# Power_Decap_2.net
KiCad netlist of a schematic drawn in Altium Designer
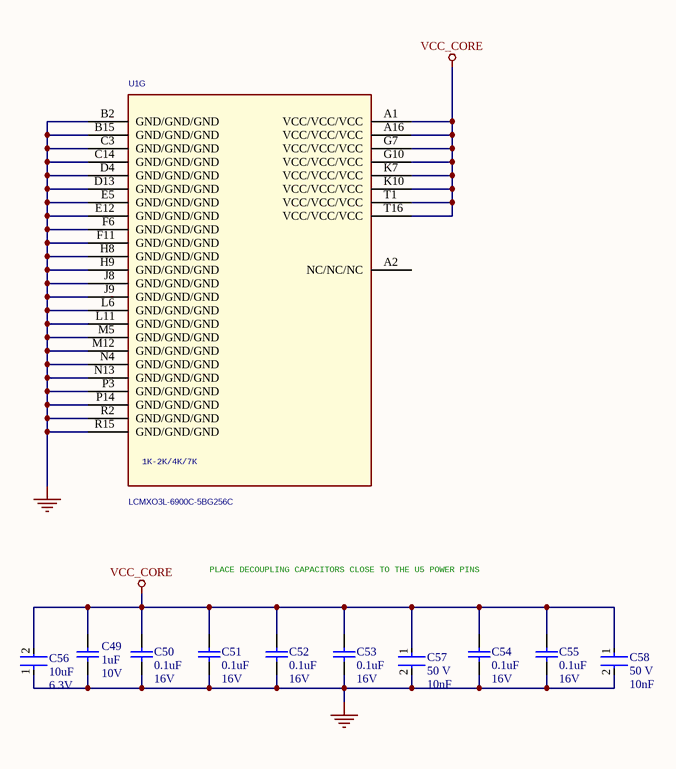
[diagram p0: Power_Decap 2.SchDoc]

(export (version "E")
  (design (tool "Eeschema 10.0.6"))
  (components
    (comp (ref "C49")
      (value "1uF")
      (footprint "CAPC1608X90X35ML15T15")
      (fields
        (field (name "MANUFACTURER") "Kemet")
        (field (name "PART NUMBER") "C0603C105K8RACTU")
        (field (name "VOLTAGE") "10V")
      )
      (libsource (lib "Altium Content Vault") (part "CAP"))
    )
    (comp (ref "C50")
      (value "0.1uF")
      (footprint "CAPC1608X87X35ML15T15")
      (description "Ceramic Capacitor 0.1uF 16V +-10% X7R0603")
      (fields
        (field (name "PART NUMBER") "C0603C104M4RACTU")
        (field (name "MANUFACTURER") "Kemet")
        (field (name "VOLTAGE") "16V")
      )
      (libsource (lib "Altium Content Vault") (part "CAP"))
    )
    (comp (ref "C51")
      (value "0.1uF")
      (footprint "CAPC1608X87X35ML15T15")
      (description "Ceramic Capacitor 0.1uF 16V +-10% X7R0603")
      (fields
        (field (name "PART NUMBER") "C0603C104M4RACTU")
        (field (name "MANUFACTURER") "Kemet")
        (field (name "VOLTAGE") "16V")
      )
      (libsource (lib "Altium Content Vault") (part "CAP"))
    )
    (comp (ref "C52")
      (value "0.1uF")
      (footprint "CAPC1608X87X35ML15T15")
      (description "Ceramic Capacitor 0.1uF 16V +-10% X7R0603")
      (fields
        (field (name "PART NUMBER") "C0603C104M4RACTU")
        (field (name "MANUFACTURER") "Kemet")
        (field (name "VOLTAGE") "16V")
      )
      (libsource (lib "Altium Content Vault") (part "CAP"))
    )
    (comp (ref "C53")
      (value "0.1uF")
      (footprint "CAPC1608X87X35ML15T15")
      (description "Ceramic Capacitor 0.1uF 16V +-10% X7R0603")
      (fields
        (field (name "PART NUMBER") "C0603C104M4RACTU")
        (field (name "MANUFACTURER") "Kemet")
        (field (name "VOLTAGE") "16V")
      )
      (libsource (lib "Altium Content Vault") (part "CAP"))
    )
    (comp (ref "C54")
      (value "0.1uF")
      (footprint "CAPC1608X87X35ML15T15")
      (description "Ceramic Capacitor 0.1uF 16V +-10% X7R0603")
      (fields
        (field (name "PART NUMBER") "C0603C104M4RACTU")
        (field (name "MANUFACTURER") "Kemet")
        (field (name "VOLTAGE") "16V")
      )
      (libsource (lib "Altium Content Vault") (part "CAP"))
    )
    (comp (ref "C55")
      (value "0.1uF")
      (footprint "CAPC1608X87X35ML15T15")
      (description "Ceramic Capacitor 0.1uF 16V +-10% X7R0603")
      (fields
        (field (name "PART NUMBER") "C0603C104M4RACTU")
        (field (name "MANUFACTURER") "Kemet")
        (field (name "VOLTAGE") "16V")
      )
      (libsource (lib "Altium Content Vault") (part "CAP"))
    )
    (comp (ref "C56")
      (value "10uF")
      (footprint "FP-CL10-IPC_C")
      (description "Cap Ceramic 10uF 6.3V X5R ±20% Pad SMD 0603 +85°C T/R")
      (fields
        (field (name "VOLTAGE") "6.3V")
        (field (name "TOLERANCE") "20%")
        (field (name "MANUFACTURER") "Samsung")
      )
      (libsource (lib "Altium Content Vault") (part "b4654b650e69147ec39a6b967a45e02"))
    )
    (comp (ref "C57")
      (value "10nF")
      (footprint "FP-C0805C-DN-MFG")
      (description "CAP CER 10000PF 50V X7R 0805")
      (fields
        (field (name "VOLTAGE") "50 V")
        (field (name "PART NUMBER") "C0805C103K5RACAUTO")
        (field (name "MANUFACTURER") "KEMET")
      )
      (libsource (lib "Altium Content Vault") (part "b4654b650e69147ec39a6b967a45e02"))
    )
    (comp (ref "C58")
      (value "10nF")
      (footprint "FP-C0805C-DN-MFG")
      (description "CAP CER 10000PF 50V X7R 0805")
      (fields
        (field (name "VOLTAGE") "50 V")
        (field (name "PART NUMBER") "C0805C103K5RACAUTO")
        (field (name "MANUFACTURER") "KEMET")
      )
      (libsource (lib "Altium Content Vault") (part "b4654b650e69147ec39a6b967a45e02"))
    )
    (comp (ref "U1")
      (value "LCMXO3L-6900C-5BG256C")
      (footprint "BGA256C80P16X16_1400X1400X170")
      (description "IC FPGA 6864LUTS 256BGA")
      (fields (field (name "MANUFACTURER") "Lattice semi"))
      (libsource (lib "*") (part "LCMXO3L-1K/2K/4K/7K-BG256"))
    )
  )
  (nets
    (net (code "1") (name "GND") (class "Default")
      (node (ref "C49") (pin "1") (pinfunction "1_1") (pintype "passive"))
      (node (ref "C50") (pin "2") (pinfunction "2_2") (pintype "passive"))
      (node (ref "C51") (pin "2") (pinfunction "2_2") (pintype "passive"))
      (node (ref "C52") (pin "2") (pinfunction "2_2") (pintype "passive"))
      (node (ref "C53") (pin "2") (pinfunction "2_2") (pintype "passive"))
      (node (ref "C54") (pin "2") (pinfunction "2_2") (pintype "passive"))
      (node (ref "C55") (pin "2") (pinfunction "2_2") (pintype "passive"))
      (node (ref "C56") (pin "1") (pinfunction "1_1") (pintype "passive"))
      (node (ref "C57") (pin "2") (pinfunction "2_2") (pintype "passive"))
      (node (ref "C58") (pin "2") (pinfunction "2_2") (pintype "passive"))
      (node (ref "U1") (pin "B15") (pinfunction "GND/GND/GND_B15") (pintype "power_in"))
      (node (ref "U1") (pin "B2") (pinfunction "GND/GND/GND_B2") (pintype "power_in"))
      (node (ref "U1") (pin "C14") (pinfunction "GND/GND/GND_C14") (pintype "power_in"))
      (node (ref "U1") (pin "C3") (pinfunction "GND/GND/GND_C3") (pintype "power_in"))
      (node (ref "U1") (pin "D13") (pinfunction "GND/GND/GND_D13") (pintype "power_in"))
      (node (ref "U1") (pin "D4") (pinfunction "GND/GND/GND_D4") (pintype "power_in"))
      (node (ref "U1") (pin "E12") (pinfunction "GND/GND/GND_E12") (pintype "power_in"))
      (node (ref "U1") (pin "E5") (pinfunction "GND/GND/GND_E5") (pintype "power_in"))
      (node (ref "U1") (pin "F11") (pinfunction "GND/GND/GND_F11") (pintype "power_in"))
      (node (ref "U1") (pin "F6") (pinfunction "GND/GND/GND_F6") (pintype "power_in"))
      (node (ref "U1") (pin "H8") (pinfunction "GND/GND/GND_H8") (pintype "power_in"))
      (node (ref "U1") (pin "H9") (pinfunction "GND/GND/GND_H9") (pintype "power_in"))
      (node (ref "U1") (pin "J8") (pinfunction "GND/GND/GND_J8") (pintype "power_in"))
      (node (ref "U1") (pin "J9") (pinfunction "GND/GND/GND_J9") (pintype "power_in"))
      (node (ref "U1") (pin "L11") (pinfunction "GND/GND/GND_L11") (pintype "power_in"))
      (node (ref "U1") (pin "L6") (pinfunction "GND/GND/GND_L6") (pintype "power_in"))
      (node (ref "U1") (pin "M12") (pinfunction "GND/GND/GND_M12") (pintype "power_in"))
      (node (ref "U1") (pin "M5") (pinfunction "GND/GND/GND_M5") (pintype "power_in"))
      (node (ref "U1") (pin "N13") (pinfunction "GND/GND/GND_N13") (pintype "power_in"))
      (node (ref "U1") (pin "N4") (pinfunction "GND/GND/GND_N4") (pintype "power_in"))
      (node (ref "U1") (pin "P14") (pinfunction "GND/GND/GND_P14") (pintype "power_in"))
      (node (ref "U1") (pin "P3") (pinfunction "GND/GND/GND_P3") (pintype "power_in"))
      (node (ref "U1") (pin "R15") (pinfunction "GND/GND/GND_R15") (pintype "power_in"))
      (node (ref "U1") (pin "R2") (pinfunction "GND/GND/GND_R2") (pintype "power_in"))
    )
    (net (code "2") (name "VCC_CORE") (class "Default")
      (node (ref "C49") (pin "2") (pinfunction "2_2") (pintype "passive"))
      (node (ref "C50") (pin "1") (pinfunction "1_1") (pintype "passive"))
      (node (ref "C51") (pin "1") (pinfunction "1_1") (pintype "passive"))
      (node (ref "C52") (pin "1") (pinfunction "1_1") (pintype "passive"))
      (node (ref "C53") (pin "1") (pinfunction "1_1") (pintype "passive"))
      (node (ref "C54") (pin "1") (pinfunction "1_1") (pintype "passive"))
      (node (ref "C55") (pin "1") (pinfunction "1_1") (pintype "passive"))
      (node (ref "C56") (pin "2") (pinfunction "2_2") (pintype "passive"))
      (node (ref "C57") (pin "1") (pinfunction "1_1") (pintype "passive"))
      (node (ref "C58") (pin "1") (pinfunction "1_1") (pintype "passive"))
      (node (ref "U1") (pin "A1") (pinfunction "VCC/VCC/VCC_A1") (pintype "power_in"))
      (node (ref "U1") (pin "A16") (pinfunction "VCC/VCC/VCC_A16") (pintype "power_in"))
      (node (ref "U1") (pin "G10") (pinfunction "VCC/VCC/VCC_G10") (pintype "power_in"))
      (node (ref "U1") (pin "G7") (pinfunction "VCC/VCC/VCC_G7") (pintype "power_in"))
      (node (ref "U1") (pin "K10") (pinfunction "VCC/VCC/VCC_K10") (pintype "power_in"))
      (node (ref "U1") (pin "K7") (pinfunction "VCC/VCC/VCC_K7") (pintype "power_in"))
      (node (ref "U1") (pin "T1") (pinfunction "VCC/VCC/VCC_T1") (pintype "power_in"))
      (node (ref "U1") (pin "T16") (pinfunction "VCC/VCC/VCC_T16") (pintype "power_in"))
    )
    (net (code "3") (name "unconnected-(U1G-NC{slash}NC{slash}NC-PadA2)") (class "Default")
      (node (ref "U1") (pin "A2") (pinfunction "NC/NC/NC_A2") (pintype "passive"))
    )
  )
)
